# LTC68xx.net
KiCad netlist of a schematic drawn in Altium Designer
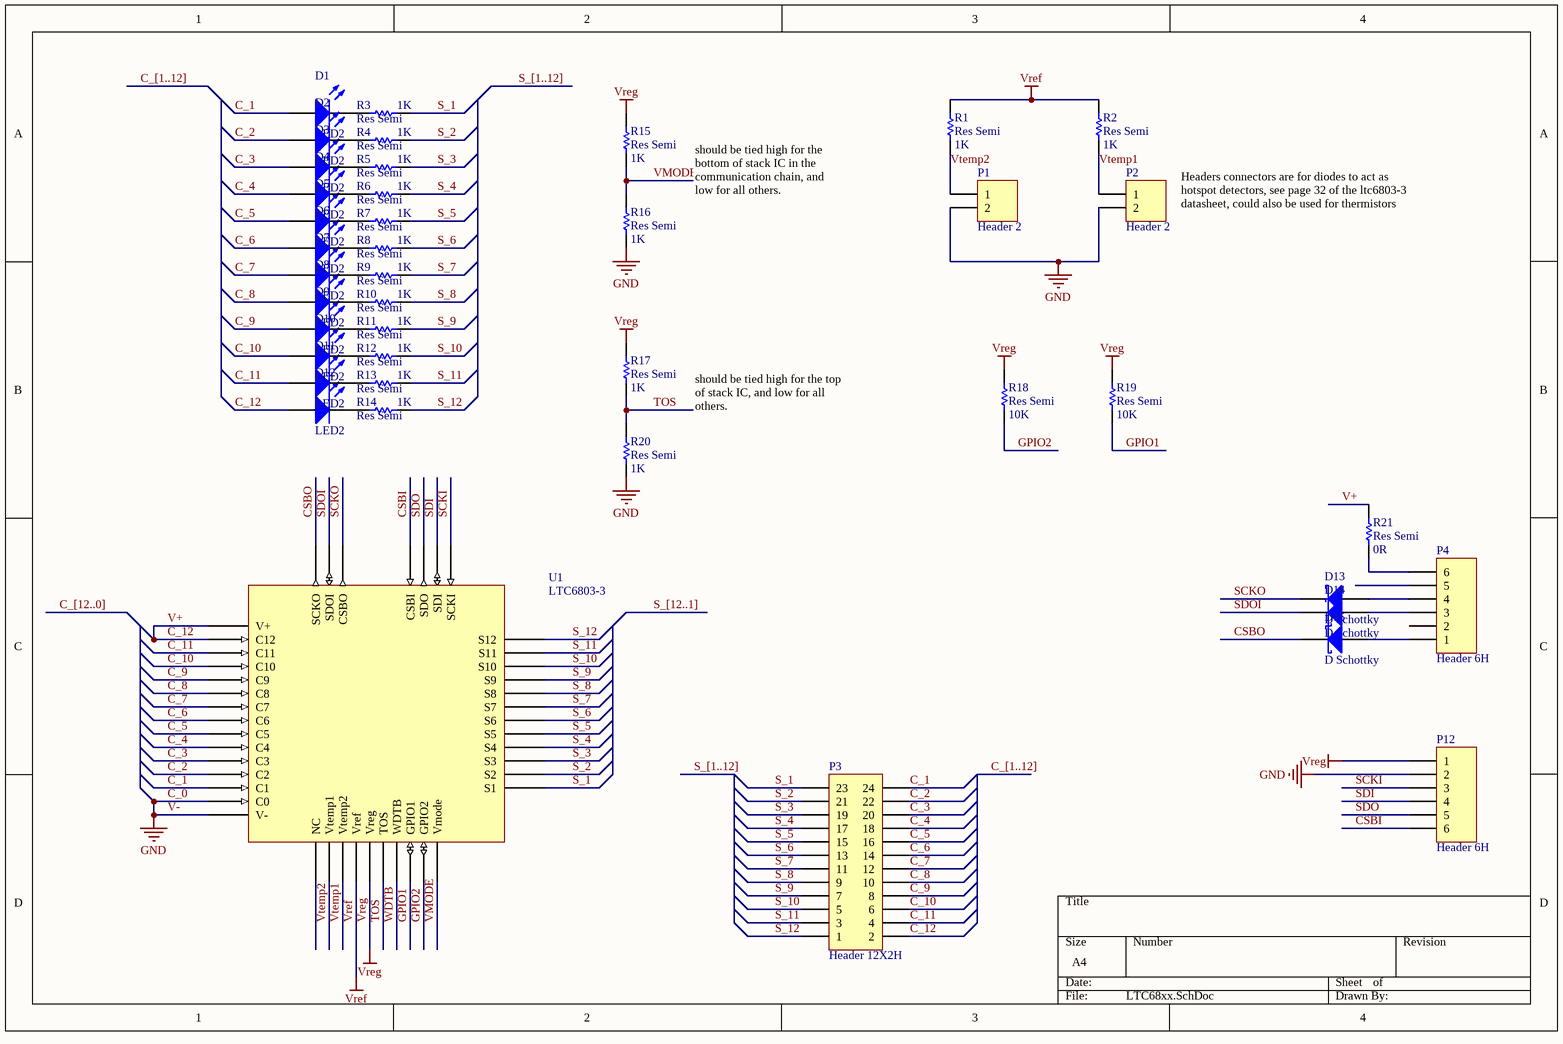
[diagram p0: LTC68xx.SchDoc]

(export (version "E")
  (design (tool "Eeschema 10.0.6"))
  (components
    (comp (ref "D1")
      (value "LED2")
      (footprint "6-0805_N")
      (description "Typical RED, GREEN, YELLOW, AMBER GaAs LED")
      (fields (field (name "PUBLISHER") "Altium Limited"))
      (libsource (lib "Miscellaneous Devices") (part "LED2"))
    )
    (comp (ref "D2")
      (value "LED2")
      (footprint "6-0805_N")
      (description "Typical RED, GREEN, YELLOW, AMBER GaAs LED")
      (fields (field (name "PUBLISHER") "Altium Limited"))
      (libsource (lib "Miscellaneous Devices") (part "LED2"))
    )
    (comp (ref "D3")
      (value "LED2")
      (footprint "6-0805_N")
      (description "Typical RED, GREEN, YELLOW, AMBER GaAs LED")
      (fields (field (name "PUBLISHER") "Altium Limited"))
      (libsource (lib "Miscellaneous Devices") (part "LED2"))
    )
    (comp (ref "D4")
      (value "LED2")
      (footprint "6-0805_N")
      (description "Typical RED, GREEN, YELLOW, AMBER GaAs LED")
      (fields (field (name "PUBLISHER") "Altium Limited"))
      (libsource (lib "Miscellaneous Devices") (part "LED2"))
    )
    (comp (ref "D5")
      (value "LED2")
      (footprint "6-0805_N")
      (description "Typical RED, GREEN, YELLOW, AMBER GaAs LED")
      (fields (field (name "PUBLISHER") "Altium Limited"))
      (libsource (lib "Miscellaneous Devices") (part "LED2"))
    )
    (comp (ref "D6")
      (value "LED2")
      (footprint "6-0805_N")
      (description "Typical RED, GREEN, YELLOW, AMBER GaAs LED")
      (fields (field (name "PUBLISHER") "Altium Limited"))
      (libsource (lib "Miscellaneous Devices") (part "LED2"))
    )
    (comp (ref "D7")
      (value "LED2")
      (footprint "6-0805_N")
      (description "Typical RED, GREEN, YELLOW, AMBER GaAs LED")
      (fields (field (name "PUBLISHER") "Altium Limited"))
      (libsource (lib "Miscellaneous Devices") (part "LED2"))
    )
    (comp (ref "D8")
      (value "LED2")
      (footprint "6-0805_N")
      (description "Typical RED, GREEN, YELLOW, AMBER GaAs LED")
      (fields (field (name "PUBLISHER") "Altium Limited"))
      (libsource (lib "Miscellaneous Devices") (part "LED2"))
    )
    (comp (ref "D9")
      (value "LED2")
      (footprint "6-0805_N")
      (description "Typical RED, GREEN, YELLOW, AMBER GaAs LED")
      (fields (field (name "PUBLISHER") "Altium Limited"))
      (libsource (lib "Miscellaneous Devices") (part "LED2"))
    )
    (comp (ref "D10")
      (value "LED2")
      (footprint "6-0805_N")
      (description "Typical RED, GREEN, YELLOW, AMBER GaAs LED")
      (fields (field (name "PUBLISHER") "Altium Limited"))
      (libsource (lib "Miscellaneous Devices") (part "LED2"))
    )
    (comp (ref "D11")
      (value "LED2")
      (footprint "6-0805_N")
      (description "Typical RED, GREEN, YELLOW, AMBER GaAs LED")
      (fields (field (name "PUBLISHER") "Altium Limited"))
      (libsource (lib "Miscellaneous Devices") (part "LED2"))
    )
    (comp (ref "D12")
      (value "LED2")
      (footprint "6-0805_N")
      (description "Typical RED, GREEN, YELLOW, AMBER GaAs LED")
      (fields (field (name "PUBLISHER") "Altium Limited"))
      (libsource (lib "Miscellaneous Devices") (part "LED2"))
    )
    (comp (ref "D13")
      (value "D Schottky")
      (footprint "SMB")
      (description "Schottky Diode")
      (fields (field (name "PUBLISHER") "Altium Limited"))
      (libsource (lib "Miscellaneous Devices") (part "D Schottky"))
    )
    (comp (ref "D14")
      (value "D Schottky")
      (footprint "SMB")
      (description "Schottky Diode")
      (fields (field (name "PUBLISHER") "Altium Limited"))
      (libsource (lib "Miscellaneous Devices") (part "D Schottky"))
    )
    (comp (ref "D15")
      (value "D Schottky")
      (footprint "SMB")
      (description "Schottky Diode")
      (fields (field (name "PUBLISHER") "Altium Limited"))
      (libsource (lib "Miscellaneous Devices") (part "D Schottky"))
    )
    (comp (ref "P1")
      (value "Header 2")
      (footprint "HDR1X2")
      (description "Header, 2-Pin")
      (fields (field (name "PUBLISHER") "Altium Limited"))
      (libsource (lib "Miscellaneous Connectors") (part "Header 2"))
    )
    (comp (ref "P2")
      (value "Header 2")
      (footprint "HDR1X2")
      (description "Header, 2-Pin")
      (fields (field (name "PUBLISHER") "Altium Limited"))
      (libsource (lib "Miscellaneous Connectors") (part "Header 2"))
    )
    (comp (ref "P3")
      (value "Header 12X2H")
      (footprint "HDR2X12H")
      (description "Header, 12-Pin, Dual row, Right Angle")
      (fields (field (name "PUBLISHER") "Altium Limited"))
      (libsource (lib "Miscellaneous Connectors") (part "Header 12X2H"))
    )
    (comp (ref "P4")
      (value "Header 6H")
      (footprint "HDR1X6H")
      (description "Header, 6-Pin, Right Angle")
      (fields (field (name "PUBLISHER") "Altium Limited"))
      (libsource (lib "") (part "Header 6H_1"))
    )
    (comp (ref "P12")
      (value "Header 6H")
      (footprint "HDR1X6H")
      (description "Header, 6-Pin, Right Angle")
      (fields (field (name "PUBLISHER") "Altium Limited"))
      (libsource (lib "Miscellaneous Connectors") (part "Header 6H"))
    )
    (comp (ref "R1")
      (value "Res Semi")
      (footprint "6-0805_L")
      (description "Semiconductor Resistor")
      (fields (field (name "ALTIUM_VALUE") "1K") (field (name "PUBLISHER") "Altium Limited"))
      (libsource (lib "Miscellaneous Devices") (part "Res Semi"))
    )
    (comp (ref "R2")
      (value "Res Semi")
      (footprint "6-0805_L")
      (description "Semiconductor Resistor")
      (fields (field (name "ALTIUM_VALUE") "1K") (field (name "PUBLISHER") "Altium Limited"))
      (libsource (lib "Miscellaneous Devices") (part "Res Semi"))
    )
    (comp (ref "R3")
      (value "Res Semi")
      (footprint "6-0805_L")
      (description "Semiconductor Resistor")
      (fields (field (name "ALTIUM_VALUE") "1K") (field (name "PUBLISHER") "Altium Limited"))
      (libsource (lib "Miscellaneous Devices") (part "Res Semi"))
    )
    (comp (ref "R4")
      (value "Res Semi")
      (footprint "6-0805_L")
      (description "Semiconductor Resistor")
      (fields (field (name "ALTIUM_VALUE") "1K") (field (name "PUBLISHER") "Altium Limited"))
      (libsource (lib "Miscellaneous Devices") (part "Res Semi"))
    )
    (comp (ref "R5")
      (value "Res Semi")
      (footprint "6-0805_L")
      (description "Semiconductor Resistor")
      (fields (field (name "ALTIUM_VALUE") "1K") (field (name "PUBLISHER") "Altium Limited"))
      (libsource (lib "Miscellaneous Devices") (part "Res Semi"))
    )
    (comp (ref "R6")
      (value "Res Semi")
      (footprint "6-0805_L")
      (description "Semiconductor Resistor")
      (fields (field (name "ALTIUM_VALUE") "1K") (field (name "PUBLISHER") "Altium Limited"))
      (libsource (lib "Miscellaneous Devices") (part "Res Semi"))
    )
    (comp (ref "R7")
      (value "Res Semi")
      (footprint "6-0805_L")
      (description "Semiconductor Resistor")
      (fields (field (name "ALTIUM_VALUE") "1K") (field (name "PUBLISHER") "Altium Limited"))
      (libsource (lib "Miscellaneous Devices") (part "Res Semi"))
    )
    (comp (ref "R8")
      (value "Res Semi")
      (footprint "6-0805_L")
      (description "Semiconductor Resistor")
      (fields (field (name "ALTIUM_VALUE") "1K") (field (name "PUBLISHER") "Altium Limited"))
      (libsource (lib "Miscellaneous Devices") (part "Res Semi"))
    )
    (comp (ref "R9")
      (value "Res Semi")
      (footprint "6-0805_L")
      (description "Semiconductor Resistor")
      (fields (field (name "ALTIUM_VALUE") "1K") (field (name "PUBLISHER") "Altium Limited"))
      (libsource (lib "Miscellaneous Devices") (part "Res Semi"))
    )
    (comp (ref "R10")
      (value "Res Semi")
      (footprint "6-0805_L")
      (description "Semiconductor Resistor")
      (fields (field (name "ALTIUM_VALUE") "1K") (field (name "PUBLISHER") "Altium Limited"))
      (libsource (lib "Miscellaneous Devices") (part "Res Semi"))
    )
    (comp (ref "R11")
      (value "Res Semi")
      (footprint "6-0805_L")
      (description "Semiconductor Resistor")
      (fields (field (name "ALTIUM_VALUE") "1K") (field (name "PUBLISHER") "Altium Limited"))
      (libsource (lib "Miscellaneous Devices") (part "Res Semi"))
    )
    (comp (ref "R12")
      (value "Res Semi")
      (footprint "6-0805_L")
      (description "Semiconductor Resistor")
      (fields (field (name "ALTIUM_VALUE") "1K") (field (name "PUBLISHER") "Altium Limited"))
      (libsource (lib "Miscellaneous Devices") (part "Res Semi"))
    )
    (comp (ref "R13")
      (value "Res Semi")
      (footprint "6-0805_L")
      (description "Semiconductor Resistor")
      (fields (field (name "ALTIUM_VALUE") "1K") (field (name "PUBLISHER") "Altium Limited"))
      (libsource (lib "Miscellaneous Devices") (part "Res Semi"))
    )
    (comp (ref "R14")
      (value "Res Semi")
      (footprint "6-0805_L")
      (description "Semiconductor Resistor")
      (fields (field (name "ALTIUM_VALUE") "1K") (field (name "PUBLISHER") "Altium Limited"))
      (libsource (lib "Miscellaneous Devices") (part "Res Semi"))
    )
    (comp (ref "R15")
      (value "Res Semi")
      (footprint "6-0805_L")
      (description "Semiconductor Resistor")
      (fields (field (name "ALTIUM_VALUE") "1K") (field (name "PUBLISHER") "Altium Limited"))
      (libsource (lib "Miscellaneous Devices") (part "Res Semi"))
    )
    (comp (ref "R16")
      (value "Res Semi")
      (footprint "6-0805_L")
      (description "Semiconductor Resistor")
      (fields (field (name "ALTIUM_VALUE") "1K") (field (name "PUBLISHER") "Altium Limited"))
      (libsource (lib "Miscellaneous Devices") (part "Res Semi"))
    )
    (comp (ref "R17")
      (value "Res Semi")
      (footprint "6-0805_L")
      (description "Semiconductor Resistor")
      (fields (field (name "ALTIUM_VALUE") "1K") (field (name "PUBLISHER") "Altium Limited"))
      (libsource (lib "Miscellaneous Devices") (part "Res Semi"))
    )
    (comp (ref "R18")
      (value "Res Semi")
      (footprint "6-0805_L")
      (description "Semiconductor Resistor")
      (fields (field (name "ALTIUM_VALUE") "10K") (field (name "PUBLISHER") "Altium Limited"))
      (libsource (lib "Miscellaneous Devices") (part "Res Semi"))
    )
    (comp (ref "R19")
      (value "Res Semi")
      (footprint "6-0805_L")
      (description "Semiconductor Resistor")
      (fields (field (name "ALTIUM_VALUE") "10K") (field (name "PUBLISHER") "Altium Limited"))
      (libsource (lib "Miscellaneous Devices") (part "Res Semi"))
    )
    (comp (ref "R20")
      (value "Res Semi")
      (footprint "6-0805_L")
      (description "Semiconductor Resistor")
      (fields (field (name "ALTIUM_VALUE") "1K") (field (name "PUBLISHER") "Altium Limited"))
      (libsource (lib "Miscellaneous Devices") (part "Res Semi"))
    )
    (comp (ref "R21")
      (value "Res Semi")
      (footprint "6-0805_L")
      (description "Semiconductor Resistor")
      (fields (field (name "ALTIUM_VALUE") "0R") (field (name "PUBLISHER") "Altium Limited"))
      (libsource (lib "Miscellaneous Devices") (part "Res Semi"))
    )
    (comp (ref "U1") (value "LTC6803-3") (footprint "SOP44") (libsource (lib "BMS") (part "LTC6803-3")))
  )
  (nets
    (net (code "1") (name "/CSBI") (class "Default")
      (node (ref "P12") (pin "6") (pinfunction "6_6") (pintype "passive"))
      (node (ref "U1") (pin "44") (pinfunction "CSBI_44") (pintype "input"))
    )
    (net (code "2") (name "/CSBO") (class "Default")
      (node (ref "D15") (pin "2") (pinfunction "K_2") (pintype "passive"))
      (node (ref "U1") (pin "3") (pinfunction "SCKO_3") (pintype "output"))
    )
    (net (code "3") (name "/C_1") (class "Default")
      (node (ref "D1") (pin "1") (pinfunction "A_1") (pintype "passive"))
      (node (ref "P3") (pin "24") (pinfunction "24_24") (pintype "passive"))
      (node (ref "U1") (pin "27") (pinfunction "C1_27") (pintype "input"))
    )
    (net (code "4") (name "/C_2") (class "Default")
      (node (ref "D2") (pin "1") (pinfunction "A_1") (pintype "passive"))
      (node (ref "P3") (pin "22") (pinfunction "22_22") (pintype "passive"))
      (node (ref "U1") (pin "25") (pinfunction "C2_25") (pintype "input"))
    )
    (net (code "5") (name "/C_3") (class "Default")
      (node (ref "D3") (pin "1") (pinfunction "A_1") (pintype "passive"))
      (node (ref "P3") (pin "20") (pinfunction "20_20") (pintype "passive"))
      (node (ref "U1") (pin "23") (pinfunction "C3_23") (pintype "input"))
    )
    (net (code "6") (name "/C_4") (class "Default")
      (node (ref "D4") (pin "1") (pinfunction "A_1") (pintype "passive"))
      (node (ref "P3") (pin "18") (pinfunction "18_18") (pintype "passive"))
      (node (ref "U1") (pin "21") (pinfunction "C4_21") (pintype "input"))
    )
    (net (code "7") (name "/C_5") (class "Default")
      (node (ref "D5") (pin "1") (pinfunction "A_1") (pintype "passive"))
      (node (ref "P3") (pin "16") (pinfunction "16_16") (pintype "passive"))
      (node (ref "U1") (pin "19") (pinfunction "C5_19") (pintype "input"))
    )
    (net (code "8") (name "/C_6") (class "Default")
      (node (ref "D6") (pin "1") (pinfunction "A_1") (pintype "passive"))
      (node (ref "P3") (pin "14") (pinfunction "14_14") (pintype "passive"))
      (node (ref "U1") (pin "17") (pinfunction "C6_17") (pintype "input"))
    )
    (net (code "9") (name "/C_7") (class "Default")
      (node (ref "D7") (pin "1") (pinfunction "A_1") (pintype "passive"))
      (node (ref "P3") (pin "12") (pinfunction "12_12") (pintype "passive"))
      (node (ref "U1") (pin "15") (pinfunction "C7_15") (pintype "input"))
    )
    (net (code "10") (name "/C_8") (class "Default")
      (node (ref "D8") (pin "1") (pinfunction "A_1") (pintype "passive"))
      (node (ref "P3") (pin "10") (pinfunction "10_10") (pintype "passive"))
      (node (ref "U1") (pin "13") (pinfunction "C8_13") (pintype "input"))
    )
    (net (code "11") (name "/C_9") (class "Default")
      (node (ref "D9") (pin "1") (pinfunction "A_1") (pintype "passive"))
      (node (ref "P3") (pin "8") (pinfunction "8_8") (pintype "passive"))
      (node (ref "U1") (pin "11") (pinfunction "C9_11") (pintype "input"))
    )
    (net (code "12") (name "/C_10") (class "Default")
      (node (ref "D10") (pin "1") (pinfunction "A_1") (pintype "passive"))
      (node (ref "P3") (pin "6") (pinfunction "6_6") (pintype "passive"))
      (node (ref "U1") (pin "9") (pinfunction "C10_9") (pintype "input"))
    )
    (net (code "13") (name "/C_11") (class "Default")
      (node (ref "D11") (pin "1") (pinfunction "A_1") (pintype "passive"))
      (node (ref "P3") (pin "4") (pinfunction "4_4") (pintype "passive"))
      (node (ref "U1") (pin "7") (pinfunction "C11_7") (pintype "input"))
    )
    (net (code "14") (name "/C_12") (class "Default")
      (node (ref "D12") (pin "1") (pinfunction "A_1") (pintype "passive"))
      (node (ref "P3") (pin "2") (pinfunction "2_2") (pintype "passive"))
      (node (ref "R21") (pin "2") (pinfunction "2_2") (pintype "passive"))
      (node (ref "U1") (pin "4") (pinfunction "V+_4") (pintype "power_in"))
      (node (ref "U1") (pin "5") (pinfunction "C12_5") (pintype "input"))
    )
    (net (code "17") (name "/GPIO1") (class "Default")
      (node (ref "R19") (pin "1") (pinfunction "1_1") (pintype "passive"))
      (node (ref "U1") (pin "38") (pinfunction "GPIO1_38") (pintype "bidirectional"))
    )
    (net (code "18") (name "/GPIO2") (class "Default")
      (node (ref "R18") (pin "1") (pinfunction "1_1") (pintype "passive"))
      (node (ref "U1") (pin "39") (pinfunction "GPIO2_39") (pintype "bidirectional"))
    )
    (net (code "19") (name "/SCKI") (class "Default")
      (node (ref "P12") (pin "3") (pinfunction "3_3") (pintype "passive"))
      (node (ref "U1") (pin "41") (pinfunction "SCKI_41") (pintype "input"))
    )
    (net (code "20") (name "/SCKO") (class "Default")
      (node (ref "D13") (pin "2") (pinfunction "K_2") (pintype "passive"))
      (node (ref "U1") (pin "1") (pinfunction "CSBO_1") (pintype "output"))
    )
    (net (code "21") (name "/SDI") (class "Default")
      (node (ref "P12") (pin "4") (pinfunction "4_4") (pintype "passive"))
      (node (ref "U1") (pin "42") (pinfunction "SDI_42") (pintype "bidirectional"))
    )
    (net (code "22") (name "/SDO") (class "Default")
      (node (ref "P12") (pin "5") (pinfunction "5_5") (pintype "passive"))
      (node (ref "U1") (pin "43") (pinfunction "SDO_43") (pintype "output"))
    )
    (net (code "23") (name "/SDOI") (class "Default")
      (node (ref "D14") (pin "2") (pinfunction "K_2") (pintype "passive"))
      (node (ref "U1") (pin "2") (pinfunction "SDOI_2") (pintype "bidirectional"))
    )
    (net (code "24") (name "/S_1") (class "Default")
      (node (ref "P3") (pin "23") (pinfunction "23_23") (pintype "passive"))
      (node (ref "R3") (pin "2") (pinfunction "2_2") (pintype "passive"))
      (node (ref "U1") (pin "28") (pinfunction "S1_28") (pintype "passive"))
    )
    (net (code "25") (name "/S_2") (class "Default")
      (node (ref "P3") (pin "21") (pinfunction "21_21") (pintype "passive"))
      (node (ref "R4") (pin "2") (pinfunction "2_2") (pintype "passive"))
      (node (ref "U1") (pin "26") (pinfunction "S2_26") (pintype "passive"))
    )
    (net (code "26") (name "/S_3") (class "Default")
      (node (ref "P3") (pin "19") (pinfunction "19_19") (pintype "passive"))
      (node (ref "R5") (pin "2") (pinfunction "2_2") (pintype "passive"))
      (node (ref "U1") (pin "24") (pinfunction "S3_24") (pintype "passive"))
    )
    (net (code "27") (name "/S_4") (class "Default")
      (node (ref "P3") (pin "17") (pinfunction "17_17") (pintype "passive"))
      (node (ref "R6") (pin "2") (pinfunction "2_2") (pintype "passive"))
      (node (ref "U1") (pin "22") (pinfunction "S4_22") (pintype "passive"))
    )
    (net (code "28") (name "/S_5") (class "Default")
      (node (ref "P3") (pin "15") (pinfunction "15_15") (pintype "passive"))
      (node (ref "R7") (pin "2") (pinfunction "2_2") (pintype "passive"))
      (node (ref "U1") (pin "20") (pinfunction "S5_20") (pintype "passive"))
    )
    (net (code "29") (name "/S_6") (class "Default")
      (node (ref "P3") (pin "13") (pinfunction "13_13") (pintype "passive"))
      (node (ref "R8") (pin "2") (pinfunction "2_2") (pintype "passive"))
      (node (ref "U1") (pin "18") (pinfunction "S6_18") (pintype "passive"))
    )
    (net (code "30") (name "/S_7") (class "Default")
      (node (ref "P3") (pin "11") (pinfunction "11_11") (pintype "passive"))
      (node (ref "R9") (pin "2") (pinfunction "2_2") (pintype "passive"))
      (node (ref "U1") (pin "16") (pinfunction "S7_16") (pintype "passive"))
    )
    (net (code "31") (name "/S_8") (class "Default")
      (node (ref "P3") (pin "9") (pinfunction "9_9") (pintype "passive"))
      (node (ref "R10") (pin "2") (pinfunction "2_2") (pintype "passive"))
      (node (ref "U1") (pin "14") (pinfunction "S8_14") (pintype "passive"))
    )
    (net (code "32") (name "/S_9") (class "Default")
      (node (ref "P3") (pin "7") (pinfunction "7_7") (pintype "passive"))
      (node (ref "R11") (pin "2") (pinfunction "2_2") (pintype "passive"))
      (node (ref "U1") (pin "12") (pinfunction "S9_12") (pintype "passive"))
    )
    (net (code "33") (name "/S_10") (class "Default")
      (node (ref "P3") (pin "5") (pinfunction "5_5") (pintype "passive"))
      (node (ref "R12") (pin "2") (pinfunction "2_2") (pintype "passive"))
      (node (ref "U1") (pin "10") (pinfunction "S10_10") (pintype "passive"))
    )
    (net (code "34") (name "/S_11") (class "Default")
      (node (ref "P3") (pin "3") (pinfunction "3_3") (pintype "passive"))
      (node (ref "R13") (pin "2") (pinfunction "2_2") (pintype "passive"))
      (node (ref "U1") (pin "8") (pinfunction "S11_8") (pintype "passive"))
    )
    (net (code "35") (name "/S_12") (class "Default")
      (node (ref "P3") (pin "1") (pinfunction "1_1") (pintype "passive"))
      (node (ref "R14") (pin "2") (pinfunction "2_2") (pintype "passive"))
      (node (ref "U1") (pin "6") (pinfunction "S12_6") (pintype "passive"))
    )
    (net (code "38") (name "/TOS") (class "Default")
      (node (ref "R17") (pin "1") (pinfunction "1_1") (pintype "passive"))
      (node (ref "R20") (pin "2") (pinfunction "2_2") (pintype "passive"))
      (node (ref "U1") (pin "36") (pinfunction "TOS_36") (pintype "passive"))
    )
    (net (code "39") (name "/VMODE") (class "Default")
      (node (ref "R15") (pin "1") (pinfunction "1_1") (pintype "passive"))
      (node (ref "R16") (pin "2") (pinfunction "2_2") (pintype "passive"))
      (node (ref "U1") (pin "40") (pinfunction "Vmode_40") (pintype "passive"))
    )
    (net (code "40") (name "/Vtemp1") (class "Default")
      (node (ref "P2") (pin "1") (pinfunction "1_1") (pintype "passive"))
      (node (ref "R2") (pin "1") (pinfunction "1_1") (pintype "passive"))
      (node (ref "U1") (pin "33") (pinfunction "Vtemp2_33") (pintype "passive"))
    )
    (net (code "41") (name "/Vtemp2") (class "Default")
      (node (ref "P1") (pin "1") (pinfunction "1_1") (pintype "passive"))
      (node (ref "R1") (pin "1") (pinfunction "1_1") (pintype "passive"))
      (node (ref "U1") (pin "32") (pinfunction "Vtemp1_32") (pintype "passive"))
    )
    (net (code "42") (name "/WDTB") (class "Default")
      (node (ref "U1") (pin "37") (pinfunction "WDTB_37") (pintype "passive"))
    )
    (net (code "43") (name "GND") (class "Default")
      (node (ref "P1") (pin "2") (pinfunction "2_2") (pintype "passive"))
      (node (ref "P12") (pin "2") (pinfunction "2_2") (pintype "passive"))
      (node (ref "P2") (pin "2") (pinfunction "2_2") (pintype "passive"))
      (node (ref "R16") (pin "1") (pinfunction "1_1") (pintype "passive"))
      (node (ref "R20") (pin "1") (pinfunction "1_1") (pintype "passive"))
      (node (ref "U1") (pin "29") (pinfunction "C0_29") (pintype "input"))
      (node (ref "U1") (pin "30") (pinfunction "V-_30") (pintype "power_in"))
    )
    (net (code "44") (name "Net-(D1-K)") (class "Default")
      (node (ref "D1") (pin "2") (pinfunction "K_2") (pintype "passive"))
      (node (ref "R3") (pin "1") (pinfunction "1_1") (pintype "passive"))
    )
    (net (code "45") (name "Net-(D2-K)") (class "Default")
      (node (ref "D2") (pin "2") (pinfunction "K_2") (pintype "passive"))
      (node (ref "R4") (pin "1") (pinfunction "1_1") (pintype "passive"))
    )
    (net (code "46") (name "Net-(D3-K)") (class "Default")
      (node (ref "D3") (pin "2") (pinfunction "K_2") (pintype "passive"))
      (node (ref "R5") (pin "1") (pinfunction "1_1") (pintype "passive"))
    )
    (net (code "47") (name "Net-(D4-K)") (class "Default")
      (node (ref "D4") (pin "2") (pinfunction "K_2") (pintype "passive"))
      (node (ref "R6") (pin "1") (pinfunction "1_1") (pintype "passive"))
    )
    (net (code "48") (name "Net-(D5-K)") (class "Default")
      (node (ref "D5") (pin "2") (pinfunction "K_2") (pintype "passive"))
      (node (ref "R7") (pin "1") (pinfunction "1_1") (pintype "passive"))
    )
    (net (code "49") (name "Net-(D6-K)") (class "Default")
      (node (ref "D6") (pin "2") (pinfunction "K_2") (pintype "passive"))
      (node (ref "R8") (pin "1") (pinfunction "1_1") (pintype "passive"))
    )
    (net (code "50") (name "Net-(D7-K)") (class "Default")
      (node (ref "D7") (pin "2") (pinfunction "K_2") (pintype "passive"))
      (node (ref "R9") (pin "1") (pinfunction "1_1") (pintype "passive"))
    )
    (net (code "51") (name "Net-(D8-K)") (class "Default")
      (node (ref "D8") (pin "2") (pinfunction "K_2") (pintype "passive"))
      (node (ref "R10") (pin "1") (pinfunction "1_1") (pintype "passive"))
    )
    (net (code "52") (name "Net-(D9-K)") (class "Default")
      (node (ref "D9") (pin "2") (pinfunction "K_2") (pintype "passive"))
      (node (ref "R11") (pin "1") (pinfunction "1_1") (pintype "passive"))
    )
    (net (code "53") (name "Net-(D10-K)") (class "Default")
      (node (ref "D10") (pin "2") (pinfunction "K_2") (pintype "passive"))
      (node (ref "R12") (pin "1") (pinfunction "1_1") (pintype "passive"))
    )
    (net (code "54") (name "Net-(D11-K)") (class "Default")
      (node (ref "D11") (pin "2") (pinfunction "K_2") (pintype "passive"))
      (node (ref "R13") (pin "1") (pinfunction "1_1") (pintype "passive"))
    )
    (net (code "55") (name "Net-(D12-K)") (class "Default")
      (node (ref "D12") (pin "2") (pinfunction "K_2") (pintype "passive"))
      (node (ref "R14") (pin "1") (pinfunction "1_1") (pintype "passive"))
    )
    (net (code "56") (name "Net-(D13-A)") (class "Default")
      (node (ref "D13") (pin "1") (pinfunction "A_1") (pintype "passive"))
      (node (ref "P4") (pin "4") (pinfunction "4_4") (pintype "passive"))
    )
    (net (code "57") (name "Net-(D14-A)") (class "Default")
      (node (ref "D14") (pin "1") (pinfunction "A_1") (pintype "passive"))
      (node (ref "P4") (pin "3") (pinfunction "3_3") (pintype "passive"))
    )
    (net (code "58") (name "Net-(D15-A)") (class "Default")
      (node (ref "D15") (pin "1") (pinfunction "A_1") (pintype "passive"))
      (node (ref "P4") (pin "1") (pinfunction "1_1") (pintype "passive"))
    )
    (net (code "59") (name "Net-(P4-Pad6)") (class "Default")
      (node (ref "P4") (pin "6") (pinfunction "6_6") (pintype "passive"))
      (node (ref "R21") (pin "1") (pinfunction "1_1") (pintype "passive"))
    )
    (net (code "60") (name "Vref") (class "Default")
      (node (ref "R1") (pin "2") (pinfunction "2_2") (pintype "passive"))
      (node (ref "R2") (pin "2") (pinfunction "2_2") (pintype "passive"))
      (node (ref "U1") (pin "34") (pinfunction "Vref_34") (pintype "passive"))
    )
    (net (code "61") (name "Vreg") (class "Default")
      (node (ref "P12") (pin "1") (pinfunction "1_1") (pintype "passive"))
      (node (ref "R15") (pin "2") (pinfunction "2_2") (pintype "passive"))
      (node (ref "R17") (pin "2") (pinfunction "2_2") (pintype "passive"))
      (node (ref "R18") (pin "2") (pinfunction "2_2") (pintype "passive"))
      (node (ref "R19") (pin "2") (pinfunction "2_2") (pintype "passive"))
      (node (ref "U1") (pin "35") (pinfunction "Vreg_35") (pintype "passive"))
    )
    (net (code "62") (name "unconnected-(P4-Pad2)") (class "Default")
      (node (ref "P4") (pin "2") (pinfunction "2_2") (pintype "passive"))
    )
    (net (code "63") (name "unconnected-(P4-Pad5)") (class "Default")
      (node (ref "P4") (pin "5") (pinfunction "5_5") (pintype "passive"))
    )
    (net (code "64") (name "unconnected-(U1-NC-Pad31)") (class "Default")
      (node (ref "U1") (pin "31") (pinfunction "NC_31") (pintype "passive"))
    )
  )
)
